# eBox_ACdetect.net
KiCad netlist of a schematic drawn in Altium Designer
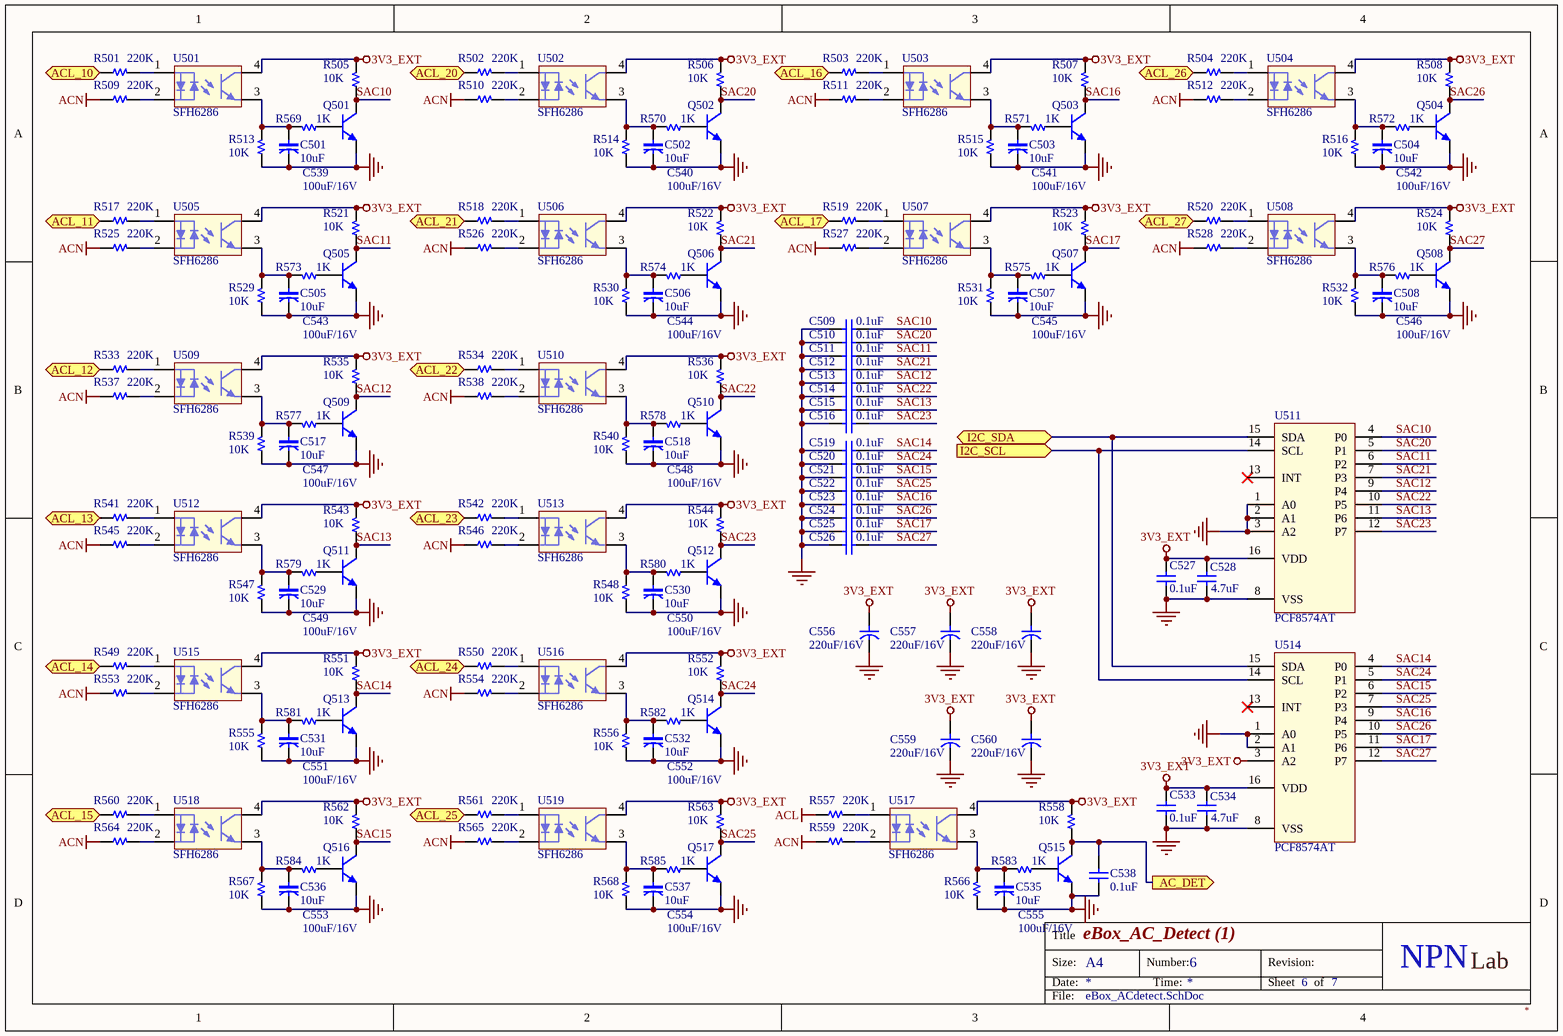
[diagram p0: eBox_ACdetect.SchDoc]

(export (version "E")
  (design (tool "Eeschema 10.0.6"))
  (components
    (comp (ref "C501")
      (value "10uF")
      (footprint "C 0805")
      (description "CAP CER 0.1UF 50V X7R 0805")
      (libsource (lib "chipfc_altium_libs") (part "Capacitor NP"))
    )
    (comp (ref "C502")
      (value "10uF")
      (footprint "C 0805")
      (description "CAP CER 0.1UF 50V X7R 0805")
      (libsource (lib "chipfc_altium_libs") (part "Capacitor NP"))
    )
    (comp (ref "C503")
      (value "10uF")
      (footprint "C 0805")
      (description "CAP CER 0.1UF 50V X7R 0805")
      (libsource (lib "chipfc_altium_libs") (part "Capacitor NP"))
    )
    (comp (ref "C504")
      (value "10uF")
      (footprint "C 0805")
      (description "CAP CER 0.1UF 50V X7R 0805")
      (libsource (lib "chipfc_altium_libs") (part "Capacitor NP"))
    )
    (comp (ref "C505")
      (value "10uF")
      (footprint "C 0805")
      (description "CAP CER 0.1UF 50V X7R 0805")
      (libsource (lib "chipfc_altium_libs") (part "Capacitor NP"))
    )
    (comp (ref "C506")
      (value "10uF")
      (footprint "C 0805")
      (description "CAP CER 0.1UF 50V X7R 0805")
      (libsource (lib "chipfc_altium_libs") (part "Capacitor NP"))
    )
    (comp (ref "C507")
      (value "10uF")
      (footprint "C 0805")
      (description "CAP CER 0.1UF 50V X7R 0805")
      (libsource (lib "chipfc_altium_libs") (part "Capacitor NP"))
    )
    (comp (ref "C508")
      (value "10uF")
      (footprint "C 0805")
      (description "CAP CER 0.1UF 50V X7R 0805")
      (libsource (lib "chipfc_altium_libs") (part "Capacitor NP"))
    )
    (comp (ref "C509")
      (value "0.1uF")
      (footprint "C 0805")
      (description "CAP CER 0.1UF 50V X7R 0805")
      (libsource (lib "chipfc_altium_libs") (part "Capacitor NP"))
    )
    (comp (ref "C510")
      (value "0.1uF")
      (footprint "C 0805")
      (description "CAP CER 0.1UF 50V X7R 0805")
      (libsource (lib "chipfc_altium_libs") (part "Capacitor NP"))
    )
    (comp (ref "C511")
      (value "0.1uF")
      (footprint "C 0805")
      (description "CAP CER 0.1UF 50V X7R 0805")
      (libsource (lib "chipfc_altium_libs") (part "Capacitor NP"))
    )
    (comp (ref "C512")
      (value "0.1uF")
      (footprint "C 0805")
      (description "CAP CER 0.1UF 50V X7R 0805")
      (libsource (lib "chipfc_altium_libs") (part "Capacitor NP"))
    )
    (comp (ref "C513")
      (value "0.1uF")
      (footprint "C 0805")
      (description "CAP CER 0.1UF 50V X7R 0805")
      (libsource (lib "chipfc_altium_libs") (part "Capacitor NP"))
    )
    (comp (ref "C514")
      (value "0.1uF")
      (footprint "C 0805")
      (description "CAP CER 0.1UF 50V X7R 0805")
      (libsource (lib "chipfc_altium_libs") (part "Capacitor NP"))
    )
    (comp (ref "C515")
      (value "0.1uF")
      (footprint "C 0805")
      (description "CAP CER 0.1UF 50V X7R 0805")
      (libsource (lib "chipfc_altium_libs") (part "Capacitor NP"))
    )
    (comp (ref "C516")
      (value "0.1uF")
      (footprint "C 0805")
      (description "CAP CER 0.1UF 50V X7R 0805")
      (libsource (lib "chipfc_altium_libs") (part "Capacitor NP"))
    )
    (comp (ref "C517")
      (value "10uF")
      (footprint "C 0805")
      (description "CAP CER 0.1UF 50V X7R 0805")
      (libsource (lib "chipfc_altium_libs") (part "Capacitor NP"))
    )
    (comp (ref "C518")
      (value "10uF")
      (footprint "C 0805")
      (description "CAP CER 0.1UF 50V X7R 0805")
      (libsource (lib "chipfc_altium_libs") (part "Capacitor NP"))
    )
    (comp (ref "C519")
      (value "0.1uF")
      (footprint "C 0805")
      (description "CAP CER 0.1UF 50V X7R 0805")
      (libsource (lib "chipfc_altium_libs") (part "Capacitor NP"))
    )
    (comp (ref "C520")
      (value "0.1uF")
      (footprint "C 0805")
      (description "CAP CER 0.1UF 50V X7R 0805")
      (libsource (lib "chipfc_altium_libs") (part "Capacitor NP"))
    )
    (comp (ref "C521")
      (value "0.1uF")
      (footprint "C 0805")
      (description "CAP CER 0.1UF 50V X7R 0805")
      (libsource (lib "chipfc_altium_libs") (part "Capacitor NP"))
    )
    (comp (ref "C522")
      (value "0.1uF")
      (footprint "C 0805")
      (description "CAP CER 0.1UF 50V X7R 0805")
      (libsource (lib "chipfc_altium_libs") (part "Capacitor NP"))
    )
    (comp (ref "C523")
      (value "0.1uF")
      (footprint "C 0805")
      (description "CAP CER 0.1UF 50V X7R 0805")
      (libsource (lib "chipfc_altium_libs") (part "Capacitor NP"))
    )
    (comp (ref "C524")
      (value "0.1uF")
      (footprint "C 0805")
      (description "CAP CER 0.1UF 50V X7R 0805")
      (libsource (lib "chipfc_altium_libs") (part "Capacitor NP"))
    )
    (comp (ref "C525")
      (value "0.1uF")
      (footprint "C 0805")
      (description "CAP CER 0.1UF 50V X7R 0805")
      (libsource (lib "chipfc_altium_libs") (part "Capacitor NP"))
    )
    (comp (ref "C526")
      (value "0.1uF")
      (footprint "C 0805")
      (description "CAP CER 0.1UF 50V X7R 0805")
      (libsource (lib "chipfc_altium_libs") (part "Capacitor NP"))
    )
    (comp (ref "C527")
      (value "0.1uF")
      (footprint "C 0603")
      (description "CAP CER 0.1UF 50V X7R 0603")
      (libsource (lib "chipfc_altium_libs") (part "Capacitor NP"))
    )
    (comp (ref "C528")
      (value "4.7uF")
      (footprint "C 0603")
      (description "CAP CER 4.7UF 50V X7R 0603")
      (libsource (lib "chipfc_altium_libs") (part "Capacitor NP"))
    )
    (comp (ref "C529")
      (value "10uF")
      (footprint "C 0805")
      (description "CAP CER 0.1UF 50V X7R 0805")
      (libsource (lib "chipfc_altium_libs") (part "Capacitor NP"))
    )
    (comp (ref "C530")
      (value "10uF")
      (footprint "C 0805")
      (description "CAP CER 0.1UF 50V X7R 0805")
      (libsource (lib "chipfc_altium_libs") (part "Capacitor NP"))
    )
    (comp (ref "C531")
      (value "10uF")
      (footprint "C 0805")
      (description "CAP CER 0.1UF 50V X7R 0805")
      (libsource (lib "chipfc_altium_libs") (part "Capacitor NP"))
    )
    (comp (ref "C532")
      (value "10uF")
      (footprint "C 0805")
      (description "CAP CER 0.1UF 50V X7R 0805")
      (libsource (lib "chipfc_altium_libs") (part "Capacitor NP"))
    )
    (comp (ref "C533")
      (value "0.1uF")
      (footprint "C 0603")
      (description "CAP CER 0.1UF 50V X7R 0603")
      (libsource (lib "chipfc_altium_libs") (part "Capacitor NP"))
    )
    (comp (ref "C534")
      (value "4.7uF")
      (footprint "C 0603")
      (description "CAP CER 4.7UF 50V X7R 0603")
      (libsource (lib "chipfc_altium_libs") (part "Capacitor NP"))
    )
    (comp (ref "C535")
      (value "10uF")
      (footprint "C 0805")
      (description "CAP CER 0.1UF 50V X7R 0805")
      (libsource (lib "chipfc_altium_libs") (part "Capacitor NP"))
    )
    (comp (ref "C536")
      (value "10uF")
      (footprint "C 0805")
      (description "CAP CER 0.1UF 50V X7R 0805")
      (libsource (lib "chipfc_altium_libs") (part "Capacitor NP"))
    )
    (comp (ref "C537")
      (value "10uF")
      (footprint "C 0805")
      (description "CAP CER 0.1UF 50V X7R 0805")
      (libsource (lib "chipfc_altium_libs") (part "Capacitor NP"))
    )
    (comp (ref "C538")
      (value "0.1uF")
      (footprint "C 0805")
      (description "CAP CER 0.1UF 50V X7R 0805")
      (libsource (lib "chipfc_altium_libs") (part "Capacitor NP"))
    )
    (comp (ref "C539")
      (value "100uF/16V")
      (footprint "CYL/D.200/LS.75")
      (description "Capacitor pol")
      (libsource (lib "chipfc_altium_libs") (part "Capacitor"))
    )
    (comp (ref "C540")
      (value "100uF/16V")
      (footprint "CYL/D.200/LS.75")
      (description "Capacitor pol")
      (libsource (lib "chipfc_altium_libs") (part "Capacitor"))
    )
    (comp (ref "C541")
      (value "100uF/16V")
      (footprint "CYL/D.200/LS.75")
      (description "Capacitor pol")
      (libsource (lib "chipfc_altium_libs") (part "Capacitor"))
    )
    (comp (ref "C542")
      (value "100uF/16V")
      (footprint "CYL/D.200/LS.75")
      (description "Capacitor pol")
      (libsource (lib "chipfc_altium_libs") (part "Capacitor"))
    )
    (comp (ref "C543")
      (value "100uF/16V")
      (footprint "CYL/D.200/LS.75")
      (description "Capacitor pol")
      (libsource (lib "chipfc_altium_libs") (part "Capacitor"))
    )
    (comp (ref "C544")
      (value "100uF/16V")
      (footprint "CYL/D.200/LS.75")
      (description "Capacitor pol")
      (libsource (lib "chipfc_altium_libs") (part "Capacitor"))
    )
    (comp (ref "C545")
      (value "100uF/16V")
      (footprint "CYL/D.200/LS.75")
      (description "Capacitor pol")
      (libsource (lib "chipfc_altium_libs") (part "Capacitor"))
    )
    (comp (ref "C546")
      (value "100uF/16V")
      (footprint "CYL/D.200/LS.75")
      (description "Capacitor pol")
      (libsource (lib "chipfc_altium_libs") (part "Capacitor"))
    )
    (comp (ref "C547")
      (value "100uF/16V")
      (footprint "CYL/D.200/LS.75")
      (description "Capacitor pol")
      (libsource (lib "chipfc_altium_libs") (part "Capacitor"))
    )
    (comp (ref "C548")
      (value "100uF/16V")
      (footprint "CYL/D.200/LS.75")
      (description "Capacitor pol")
      (libsource (lib "chipfc_altium_libs") (part "Capacitor"))
    )
    (comp (ref "C549")
      (value "100uF/16V")
      (footprint "CYL/D.200/LS.75")
      (description "Capacitor pol")
      (libsource (lib "chipfc_altium_libs") (part "Capacitor"))
    )
    (comp (ref "C550")
      (value "100uF/16V")
      (footprint "CYL/D.200/LS.75")
      (description "Capacitor pol")
      (libsource (lib "chipfc_altium_libs") (part "Capacitor"))
    )
    (comp (ref "C551")
      (value "100uF/16V")
      (footprint "CYL/D.200/LS.75")
      (description "Capacitor pol")
      (libsource (lib "chipfc_altium_libs") (part "Capacitor"))
    )
    (comp (ref "C552")
      (value "100uF/16V")
      (footprint "CYL/D.200/LS.75")
      (description "Capacitor pol")
      (libsource (lib "chipfc_altium_libs") (part "Capacitor"))
    )
    (comp (ref "C553")
      (value "100uF/16V")
      (footprint "CYL/D.200/LS.75")
      (description "Capacitor pol")
      (libsource (lib "chipfc_altium_libs") (part "Capacitor"))
    )
    (comp (ref "C554")
      (value "100uF/16V")
      (footprint "CYL/D.200/LS.75")
      (description "Capacitor pol")
      (libsource (lib "chipfc_altium_libs") (part "Capacitor"))
    )
    (comp (ref "C555")
      (value "100uF/16V")
      (footprint "CYL/D.200/LS.75")
      (description "Capacitor pol")
      (libsource (lib "chipfc_altium_libs") (part "Capacitor"))
    )
    (comp (ref "C556")
      (value "220uF/16V")
      (footprint "CYL/D.250/LS.100")
      (description "CAP TANT 100UF 20% 16V 2917")
      (libsource (lib "") (part "Capacitor_1"))
    )
    (comp (ref "C557")
      (value "220uF/16V")
      (footprint "CYL/D.250/LS.100")
      (description "CAP TANT 100UF 20% 16V 2917")
      (libsource (lib "") (part "Capacitor_1"))
    )
    (comp (ref "C558")
      (value "220uF/16V")
      (footprint "CYL/D.250/LS.100")
      (description "CAP TANT 100UF 20% 16V 2917")
      (libsource (lib "") (part "Capacitor_1"))
    )
    (comp (ref "C559")
      (value "220uF/16V")
      (footprint "CYL/D.250/LS.100")
      (description "CAP TANT 100UF 20% 16V 2917")
      (libsource (lib "") (part "Capacitor_1"))
    )
    (comp (ref "C560")
      (value "220uF/16V")
      (footprint "CYL/D.250/LS.100")
      (description "CAP TANT 100UF 20% 16V 2917")
      (libsource (lib "") (part "Capacitor_1"))
    )
    (comp (ref "Q501")
      (value "MMBT3904LT1G")
      (footprint "SOT-23")
      (description "TRANS NPN 40V 0.2A SOT23")
      (libsource (lib "chipfc_altium_libs") (part "Transistor NPN"))
    )
    (comp (ref "Q502")
      (value "MMBT3904LT1G")
      (footprint "SOT-23")
      (description "TRANS NPN 40V 0.2A SOT23")
      (libsource (lib "chipfc_altium_libs") (part "Transistor NPN"))
    )
    (comp (ref "Q503")
      (value "MMBT3904LT1G")
      (footprint "SOT-23")
      (description "TRANS NPN 40V 0.2A SOT23")
      (libsource (lib "chipfc_altium_libs") (part "Transistor NPN"))
    )
    (comp (ref "Q504")
      (value "MMBT3904LT1G")
      (footprint "SOT-23")
      (description "TRANS NPN 40V 0.2A SOT23")
      (libsource (lib "chipfc_altium_libs") (part "Transistor NPN"))
    )
    (comp (ref "Q505")
      (value "MMBT3904LT1G")
      (footprint "SOT-23")
      (description "TRANS NPN 40V 0.2A SOT23")
      (libsource (lib "chipfc_altium_libs") (part "Transistor NPN"))
    )
    (comp (ref "Q506")
      (value "MMBT3904LT1G")
      (footprint "SOT-23")
      (description "TRANS NPN 40V 0.2A SOT23")
      (libsource (lib "chipfc_altium_libs") (part "Transistor NPN"))
    )
    (comp (ref "Q507")
      (value "MMBT3904LT1G")
      (footprint "SOT-23")
      (description "TRANS NPN 40V 0.2A SOT23")
      (libsource (lib "chipfc_altium_libs") (part "Transistor NPN"))
    )
    (comp (ref "Q508")
      (value "MMBT3904LT1G")
      (footprint "SOT-23")
      (description "TRANS NPN 40V 0.2A SOT23")
      (libsource (lib "chipfc_altium_libs") (part "Transistor NPN"))
    )
    (comp (ref "Q509")
      (value "MMBT3904LT1G")
      (footprint "SOT-23")
      (description "TRANS NPN 40V 0.2A SOT23")
      (libsource (lib "chipfc_altium_libs") (part "Transistor NPN"))
    )
    (comp (ref "Q510")
      (value "MMBT3904LT1G")
      (footprint "SOT-23")
      (description "TRANS NPN 40V 0.2A SOT23")
      (libsource (lib "chipfc_altium_libs") (part "Transistor NPN"))
    )
    (comp (ref "Q511")
      (value "MMBT3904LT1G")
      (footprint "SOT-23")
      (description "TRANS NPN 40V 0.2A SOT23")
      (libsource (lib "chipfc_altium_libs") (part "Transistor NPN"))
    )
    (comp (ref "Q512")
      (value "MMBT3904LT1G")
      (footprint "SOT-23")
      (description "TRANS NPN 40V 0.2A SOT23")
      (libsource (lib "chipfc_altium_libs") (part "Transistor NPN"))
    )
    (comp (ref "Q513")
      (value "MMBT3904LT1G")
      (footprint "SOT-23")
      (description "TRANS NPN 40V 0.2A SOT23")
      (libsource (lib "chipfc_altium_libs") (part "Transistor NPN"))
    )
    (comp (ref "Q514")
      (value "MMBT3904LT1G")
      (footprint "SOT-23")
      (description "TRANS NPN 40V 0.2A SOT23")
      (libsource (lib "chipfc_altium_libs") (part "Transistor NPN"))
    )
    (comp (ref "Q515")
      (value "MMBT3904LT1G")
      (footprint "SOT-23")
      (description "TRANS NPN 40V 0.2A SOT23")
      (libsource (lib "chipfc_altium_libs") (part "Transistor NPN"))
    )
    (comp (ref "Q516")
      (value "MMBT3904LT1G")
      (footprint "SOT-23")
      (description "TRANS NPN 40V 0.2A SOT23")
      (libsource (lib "chipfc_altium_libs") (part "Transistor NPN"))
    )
    (comp (ref "Q517")
      (value "MMBT3904LT1G")
      (footprint "SOT-23")
      (description "TRANS NPN 40V 0.2A SOT23")
      (libsource (lib "chipfc_altium_libs") (part "Transistor NPN"))
    )
    (comp (ref "R501")
      (value "220K")
      (footprint "R 0805")
      (description "RES SMD 220K OHM 1% 1/8W 0805")
      (libsource (lib "chipfc_altium_libs") (part "Resistor"))
    )
    (comp (ref "R502")
      (value "220K")
      (footprint "R 0805")
      (description "RES SMD 220K OHM 1% 1/8W 0805")
      (libsource (lib "chipfc_altium_libs") (part "Resistor"))
    )
    (comp (ref "R503")
      (value "220K")
      (footprint "R 0805")
      (description "RES SMD 220K OHM 1% 1/8W 0805")
      (libsource (lib "chipfc_altium_libs") (part "Resistor"))
    )
    (comp (ref "R504")
      (value "220K")
      (footprint "R 0805")
      (description "RES SMD 220K OHM 1% 1/8W 0805")
      (libsource (lib "chipfc_altium_libs") (part "Resistor"))
    )
    (comp (ref "R505")
      (value "10K")
      (footprint "R 0805")
      (description "RES SMD 10K OHM 1% 1/8W 0805")
      (libsource (lib "chipfc_altium_libs") (part "Resistor"))
    )
    (comp (ref "R506")
      (value "10K")
      (footprint "R 0805")
      (description "RES SMD 10K OHM 1% 1/8W 0805")
      (libsource (lib "chipfc_altium_libs") (part "Resistor"))
    )
    (comp (ref "R507")
      (value "10K")
      (footprint "R 0805")
      (description "RES SMD 10K OHM 1% 1/8W 0805")
      (libsource (lib "chipfc_altium_libs") (part "Resistor"))
    )
    (comp (ref "R508")
      (value "10K")
      (footprint "R 0805")
      (description "RES SMD 10K OHM 1% 1/8W 0805")
      (libsource (lib "chipfc_altium_libs") (part "Resistor"))
    )
    (comp (ref "R509")
      (value "220K")
      (footprint "R 0805")
      (description "RES SMD 220K OHM 1% 1/8W 0805")
      (libsource (lib "chipfc_altium_libs") (part "Resistor"))
    )
    (comp (ref "R510")
      (value "220K")
      (footprint "R 0805")
      (description "RES SMD 220K OHM 1% 1/8W 0805")
      (libsource (lib "chipfc_altium_libs") (part "Resistor"))
    )
    (comp (ref "R511")
      (value "220K")
      (footprint "R 0805")
      (description "RES SMD 220K OHM 1% 1/8W 0805")
      (libsource (lib "chipfc_altium_libs") (part "Resistor"))
    )
    (comp (ref "R512")
      (value "220K")
      (footprint "R 0805")
      (description "RES SMD 220K OHM 1% 1/8W 0805")
      (libsource (lib "chipfc_altium_libs") (part "Resistor"))
    )
    (comp (ref "R513")
      (value "10K")
      (footprint "R 0805")
      (description "RES SMD 10K OHM 1% 1/8W 0805")
      (libsource (lib "chipfc_altium_libs") (part "Resistor"))
    )
    (comp (ref "R514")
      (value "10K")
      (footprint "R 0805")
      (description "RES SMD 10K OHM 1% 1/8W 0805")
      (libsource (lib "chipfc_altium_libs") (part "Resistor"))
    )
    (comp (ref "R515")
      (value "10K")
      (footprint "R 0805")
      (description "RES SMD 10K OHM 1% 1/8W 0805")
      (libsource (lib "chipfc_altium_libs") (part "Resistor"))
    )
    (comp (ref "R516")
      (value "10K")
      (footprint "R 0805")
      (description "RES SMD 10K OHM 1% 1/8W 0805")
      (libsource (lib "chipfc_altium_libs") (part "Resistor"))
    )
    (comp (ref "R517")
      (value "220K")
      (footprint "R 0805")
      (description "RES SMD 220K OHM 1% 1/8W 0805")
      (libsource (lib "chipfc_altium_libs") (part "Resistor"))
    )
    (comp (ref "R518")
      (value "220K")
      (footprint "R 0805")
      (description "RES SMD 220K OHM 1% 1/8W 0805")
      (libsource (lib "chipfc_altium_libs") (part "Resistor"))
    )
    (comp (ref "R519")
      (value "220K")
      (footprint "R 0805")
      (description "RES SMD 220K OHM 1% 1/8W 0805")
      (libsource (lib "chipfc_altium_libs") (part "Resistor"))
    )
    (comp (ref "R520")
      (value "220K")
      (footprint "R 0805")
      (description "RES SMD 220K OHM 1% 1/8W 0805")
      (libsource (lib "chipfc_altium_libs") (part "Resistor"))
    )
    (comp (ref "R521")
      (value "10K")
      (footprint "R 0805")
      (description "RES SMD 10K OHM 1% 1/8W 0805")
      (libsource (lib "chipfc_altium_libs") (part "Resistor"))
    )
    (comp (ref "R522")
      (value "10K")
      (footprint "R 0805")
      (description "RES SMD 10K OHM 1% 1/8W 0805")
      (libsource (lib "chipfc_altium_libs") (part "Resistor"))
    )
    (comp (ref "R523")
      (value "10K")
      (footprint "R 0805")
      (description "RES SMD 10K OHM 1% 1/8W 0805")
      (libsource (lib "chipfc_altium_libs") (part "Resistor"))
    )
    (comp (ref "R524")
      (value "10K")
      (footprint "R 0805")
      (description "RES SMD 10K OHM 1% 1/8W 0805")
      (libsource (lib "chipfc_altium_libs") (part "Resistor"))
    )
    (comp (ref "R525")
      (value "220K")
      (footprint "R 0805")
      (description "RES SMD 220K OHM 1% 1/8W 0805")
      (libsource (lib "chipfc_altium_libs") (part "Resistor"))
    )
    (comp (ref "R526")
      (value "220K")
      (footprint "R 0805")
      (description "RES SMD 220K OHM 1% 1/8W 0805")
      (libsource (lib "chipfc_altium_libs") (part "Resistor"))
    )
    (comp (ref "R527")
      (value "220K")
      (footprint "R 0805")
      (description "RES SMD 220K OHM 1% 1/8W 0805")
      (libsource (lib "chipfc_altium_libs") (part "Resistor"))
    )
    (comp (ref "R528")
      (value "220K")
      (footprint "R 0805")
      (description "RES SMD 220K OHM 1% 1/8W 0805")
      (libsource (lib "chipfc_altium_libs") (part "Resistor"))
    )
    (comp (ref "R529")
      (value "10K")
      (footprint "R 0805")
      (description "RES SMD 10K OHM 1% 1/8W 0805")
      (libsource (lib "chipfc_altium_libs") (part "Resistor"))
    )
    (comp (ref "R530")
      (value "10K")
      (footprint "R 0805")
      (description "RES SMD 10K OHM 1% 1/8W 0805")
      (libsource (lib "chipfc_altium_libs") (part "Resistor"))
    )
    (comp (ref "R531")
      (value "10K")
      (footprint "R 0805")
      (description "RES SMD 10K OHM 1% 1/8W 0805")
      (libsource (lib "chipfc_altium_libs") (part "Resistor"))
    )
    (comp (ref "R532")
      (value "10K")
      (footprint "R 0805")
      (description "RES SMD 10K OHM 1% 1/8W 0805")
      (libsource (lib "chipfc_altium_libs") (part "Resistor"))
    )
    (comp (ref "R533")
      (value "220K")
      (footprint "R 0805")
      (description "RES SMD 220K OHM 1% 1/8W 0805")
      (libsource (lib "chipfc_altium_libs") (part "Resistor"))
    )
    (comp (ref "R534")
      (value "220K")
      (footprint "R 0805")
      (description "RES SMD 220K OHM 1% 1/8W 0805")
      (libsource (lib "chipfc_altium_libs") (part "Resistor"))
    )
    (comp (ref "R535")
      (value "10K")
      (footprint "R 0805")
      (description "RES SMD 10K OHM 1% 1/8W 0805")
      (libsource (lib "chipfc_altium_libs") (part "Resistor"))
    )
    (comp (ref "R536")
      (value "10K")
      (footprint "R 0805")
      (description "RES SMD 10K OHM 1% 1/8W 0805")
      (libsource (lib "chipfc_altium_libs") (part "Resistor"))
    )
    (comp (ref "R537")
      (value "220K")
      (footprint "R 0805")
      (description "RES SMD 220K OHM 1% 1/8W 0805")
      (libsource (lib "chipfc_altium_libs") (part "Resistor"))
    )
    (comp (ref "R538")
      (value "220K")
      (footprint "R 0805")
      (description "RES SMD 220K OHM 1% 1/8W 0805")
      (libsource (lib "chipfc_altium_libs") (part "Resistor"))
    )
    (comp (ref "R539")
      (value "10K")
      (footprint "R 0805")
      (description "RES SMD 10K OHM 1% 1/8W 0805")
      (libsource (lib "chipfc_altium_libs") (part "Resistor"))
    )
    (comp (ref "R540")
      (value "10K")
      (footprint "R 0805")
      (description "RES SMD 10K OHM 1% 1/8W 0805")
      (libsource (lib "chipfc_altium_libs") (part "Resistor"))
    )
    (comp (ref "R541")
      (value "220K")
      (footprint "R 0805")
      (description "RES SMD 220K OHM 1% 1/8W 0805")
      (libsource (lib "chipfc_altium_libs") (part "Resistor"))
    )
    (comp (ref "R542")
      (value "220K")
      (footprint "R 0805")
      (description "RES SMD 220K OHM 1% 1/8W 0805")
      (libsource (lib "chipfc_altium_libs") (part "Resistor"))
    )
    (comp (ref "R543")
      (value "10K")
      (footprint "R 0805")
      (description "RES SMD 10K OHM 1% 1/8W 0805")
      (libsource (lib "chipfc_altium_libs") (part "Resistor"))
    )
    (comp (ref "R544")
      (value "10K")
      (footprint "R 0805")
      (description "RES SMD 10K OHM 1% 1/8W 0805")
      (libsource (lib "chipfc_altium_libs") (part "Resistor"))
    )
    (comp (ref "R545")
      (value "220K")
      (footprint "R 0805")
      (description "RES SMD 220K OHM 1% 1/8W 0805")
      (libsource (lib "chipfc_altium_libs") (part "Resistor"))
    )
    (comp (ref "R546")
      (value "220K")
      (footprint "R 0805")
      (description "RES SMD 220K OHM 1% 1/8W 0805")
      (libsource (lib "chipfc_altium_libs") (part "Resistor"))
    )
    (comp (ref "R547")
      (value "10K")
      (footprint "R 0805")
      (description "RES SMD 10K OHM 1% 1/8W 0805")
      (libsource (lib "chipfc_altium_libs") (part "Resistor"))
    )
    (comp (ref "R548")
      (value "10K")
      (footprint "R 0805")
      (description "RES SMD 10K OHM 1% 1/8W 0805")
      (libsource (lib "chipfc_altium_libs") (part "Resistor"))
    )
    (comp (ref "R549")
      (value "220K")
      (footprint "R 0805")
      (description "RES SMD 220K OHM 1% 1/8W 0805")
      (libsource (lib "chipfc_altium_libs") (part "Resistor"))
    )
    (comp (ref "R550")
      (value "220K")
      (footprint "R 0805")
      (description "RES SMD 220K OHM 1% 1/8W 0805")
      (libsource (lib "chipfc_altium_libs") (part "Resistor"))
    )
    (comp (ref "R551")
      (value "10K")
      (footprint "R 0805")
      (description "RES SMD 10K OHM 1% 1/8W 0805")
      (libsource (lib "chipfc_altium_libs") (part "Resistor"))
    )
    (comp (ref "R552")
      (value "10K")
      (footprint "R 0805")
      (description "RES SMD 10K OHM 1% 1/8W 0805")
      (libsource (lib "chipfc_altium_libs") (part "Resistor"))
    )
    (comp (ref "R553")
      (value "220K")
      (footprint "R 0805")
      (description "RES SMD 220K OHM 1% 1/8W 0805")
      (libsource (lib "chipfc_altium_libs") (part "Resistor"))
    )
    (comp (ref "R554")
      (value "220K")
      (footprint "R 0805")
      (description "RES SMD 220K OHM 1% 1/8W 0805")
      (libsource (lib "chipfc_altium_libs") (part "Resistor"))
    )
    (comp (ref "R555")
      (value "10K")
      (footprint "R 0805")
      (description "RES SMD 10K OHM 1% 1/8W 0805")
      (libsource (lib "chipfc_altium_libs") (part "Resistor"))
    )
    (comp (ref "R556")
      (value "10K")
      (footprint "R 0805")
      (description "RES SMD 10K OHM 1% 1/8W 0805")
      (libsource (lib "chipfc_altium_libs") (part "Resistor"))
    )
    (comp (ref "R557")
      (value "220K")
      (footprint "R 0805")
      (description "RES SMD 220K OHM 1% 1/8W 0805")
      (libsource (lib "chipfc_altium_libs") (part "Resistor"))
    )
    (comp (ref "R558")
      (value "10K")
      (footprint "R 0805")
      (description "RES SMD 10K OHM 1% 1/8W 0805")
      (libsource (lib "chipfc_altium_libs") (part "Resistor"))
    )
    (comp (ref "R559")
      (value "220K")
      (footprint "R 0805")
      (description "RES SMD 220K OHM 1% 1/8W 0805")
      (libsource (lib "chipfc_altium_libs") (part "Resistor"))
    )
    (comp (ref "R560")
      (value "220K")
      (footprint "R 0805")
      (description "RES SMD 220K OHM 1% 1/8W 0805")
      (libsource (lib "chipfc_altium_libs") (part "Resistor"))
    )
    (comp (ref "R561")
      (value "220K")
      (footprint "R 0805")
      (description "RES SMD 220K OHM 1% 1/8W 0805")
      (libsource (lib "chipfc_altium_libs") (part "Resistor"))
    )
    (comp (ref "R562")
      (value "10K")
      (footprint "R 0805")
      (description "RES SMD 10K OHM 1% 1/8W 0805")
      (libsource (lib "chipfc_altium_libs") (part "Resistor"))
    )
    (comp (ref "R563")
      (value "10K")
      (footprint "R 0805")
      (description "RES SMD 10K OHM 1% 1/8W 0805")
      (libsource (lib "chipfc_altium_libs") (part "Resistor"))
    )
    (comp (ref "R564")
      (value "220K")
      (footprint "R 0805")
      (description "RES SMD 220K OHM 1% 1/8W 0805")
      (libsource (lib "chipfc_altium_libs") (part "Resistor"))
    )
    (comp (ref "R565")
      (value "220K")
      (footprint "R 0805")
      (description "RES SMD 220K OHM 1% 1/8W 0805")
      (libsource (lib "chipfc_altium_libs") (part "Resistor"))
    )
    (comp (ref "R566")
      (value "10K")
      (footprint "R 0805")
      (description "RES SMD 10K OHM 1% 1/8W 0805")
      (libsource (lib "chipfc_altium_libs") (part "Resistor"))
    )
    (comp (ref "R567")
      (value "10K")
      (footprint "R 0805")
      (description "RES SMD 10K OHM 1% 1/8W 0805")
      (libsource (lib "chipfc_altium_libs") (part "Resistor"))
    )
    (comp (ref "R568")
      (value "10K")
      (footprint "R 0805")
      (description "RES SMD 10K OHM 1% 1/8W 0805")
      (libsource (lib "chipfc_altium_libs") (part "Resistor"))
    )
    (comp (ref "R569")
      (value "1K")
      (footprint "R 0805")
      (description "RES SMD 10K OHM 1% 1/8W 0805")
      (libsource (lib "chipfc_altium_libs") (part "Resistor"))
    )
    (comp (ref "R570")
      (value "1K")
      (footprint "R 0805")
      (description "RES SMD 10K OHM 1% 1/8W 0805")
      (libsource (lib "chipfc_altium_libs") (part "Resistor"))
    )
    (comp (ref "R571")
      (value "1K")
      (footprint "R 0805")
      (description "RES SMD 10K OHM 1% 1/8W 0805")
      (libsource (lib "chipfc_altium_libs") (part "Resistor"))
    )
    (comp (ref "R572")
      (value "1K")
      (footprint "R 0805")
      (description "RES SMD 10K OHM 1% 1/8W 0805")
      (libsource (lib "chipfc_altium_libs") (part "Resistor"))
    )
    (comp (ref "R573")
      (value "1K")
      (footprint "R 0805")
      (description "RES SMD 10K OHM 1% 1/8W 0805")
      (libsource (lib "chipfc_altium_libs") (part "Resistor"))
    )
    (comp (ref "R574")
      (value "1K")
      (footprint "R 0805")
      (description "RES SMD 10K OHM 1% 1/8W 0805")
      (libsource (lib "chipfc_altium_libs") (part "Resistor"))
    )
    (comp (ref "R575")
      (value "1K")
      (footprint "R 0805")
      (description "RES SMD 10K OHM 1% 1/8W 0805")
      (libsource (lib "chipfc_altium_libs") (part "Resistor"))
    )
    (comp (ref "R576")
      (value "1K")
      (footprint "R 0805")
      (description "RES SMD 10K OHM 1% 1/8W 0805")
      (libsource (lib "chipfc_altium_libs") (part "Resistor"))
    )
    (comp (ref "R577")
      (value "1K")
      (footprint "R 0805")
      (description "RES SMD 10K OHM 1% 1/8W 0805")
      (libsource (lib "chipfc_altium_libs") (part "Resistor"))
    )
    (comp (ref "R578")
      (value "1K")
      (footprint "R 0805")
      (description "RES SMD 10K OHM 1% 1/8W 0805")
      (libsource (lib "chipfc_altium_libs") (part "Resistor"))
    )
    (comp (ref "R579")
      (value "1K")
      (footprint "R 0805")
      (description "RES SMD 10K OHM 1% 1/8W 0805")
      (libsource (lib "chipfc_altium_libs") (part "Resistor"))
    )
    (comp (ref "R580")
      (value "1K")
      (footprint "R 0805")
      (description "RES SMD 10K OHM 1% 1/8W 0805")
      (libsource (lib "chipfc_altium_libs") (part "Resistor"))
    )
    (comp (ref "R581")
      (value "1K")
      (footprint "R 0805")
      (description "RES SMD 10K OHM 1% 1/8W 0805")
      (libsource (lib "chipfc_altium_libs") (part "Resistor"))
    )
    (comp (ref "R582")
      (value "1K")
      (footprint "R 0805")
      (description "RES SMD 10K OHM 1% 1/8W 0805")
      (libsource (lib "chipfc_altium_libs") (part "Resistor"))
    )
    (comp (ref "R583")
      (value "1K")
      (footprint "R 0805")
      (description "RES SMD 10K OHM 1% 1/8W 0805")
      (libsource (lib "chipfc_altium_libs") (part "Resistor"))
    )
    (comp (ref "R584")
      (value "1K")
      (footprint "R 0805")
      (description "RES SMD 10K OHM 1% 1/8W 0805")
      (libsource (lib "chipfc_altium_libs") (part "Resistor"))
    )
    (comp (ref "R585")
      (value "1K")
      (footprint "R 0805")
      (description "RES SMD 10K OHM 1% 1/8W 0805")
      (libsource (lib "chipfc_altium_libs") (part "Resistor"))
    )
    (comp (ref "U501")
      (value "SFH6286")
      (footprint "SOP4 - SFH6286")
      (libsource (lib "chipfc_altium_libs") (part "SFH6286"))
    )
    (comp (ref "U502")
      (value "SFH6286")
      (footprint "SOP4 - SFH6286")
      (libsource (lib "chipfc_altium_libs") (part "SFH6286"))
    )
    (comp (ref "U503")
      (value "SFH6286")
      (footprint "SOP4 - SFH6286")
      (libsource (lib "chipfc_altium_libs") (part "SFH6286"))
    )
    (comp (ref "U504")
      (value "SFH6286")
      (footprint "SOP4 - SFH6286")
      (libsource (lib "chipfc_altium_libs") (part "SFH6286"))
    )
    (comp (ref "U505")
      (value "SFH6286")
      (footprint "SOP4 - SFH6286")
      (libsource (lib "chipfc_altium_libs") (part "SFH6286"))
    )
    (comp (ref "U506")
      (value "SFH6286")
      (footprint "SOP4 - SFH6286")
      (libsource (lib "chipfc_altium_libs") (part "SFH6286"))
    )
    (comp (ref "U507")
      (value "SFH6286")
      (footprint "SOP4 - SFH6286")
      (libsource (lib "chipfc_altium_libs") (part "SFH6286"))
    )
    (comp (ref "U508")
      (value "SFH6286")
      (footprint "SOP4 - SFH6286")
      (libsource (lib "chipfc_altium_libs") (part "SFH6286"))
    )
    (comp (ref "U509")
      (value "SFH6286")
      (footprint "SOP4 - SFH6286")
      (libsource (lib "chipfc_altium_libs") (part "SFH6286"))
    )
    (comp (ref "U510")
      (value "SFH6286")
      (footprint "SOP4 - SFH6286")
      (libsource (lib "chipfc_altium_libs") (part "SFH6286"))
    )
    (comp (ref "U511")
      (value "PCF8574AT")
      (footprint "SO16/PCF8574AT")
      (description "Remote 8-bit I/O expander for I2C-bus with interrupt")
      (fields (field (name "PART NO") "PCF8574AT/3"))
      (libsource (lib "chipfc_altium_libs") (part "PCF8574AT"))
    )
    (comp (ref "U512")
      (value "SFH6286")
      (footprint "SOP4 - SFH6286")
      (libsource (lib "chipfc_altium_libs") (part "SFH6286"))
    )
    (comp (ref "U513")
      (value "SFH6286")
      (footprint "SOP4 - SFH6286")
      (libsource (lib "chipfc_altium_libs") (part "SFH6286"))
    )
    (comp (ref "U514")
      (value "PCF8574AT")
      (footprint "SO16/PCF8574AT")
      (description "Remote 8-bit I/O expander for I2C-bus with interrupt")
      (fields (field (name "PART NO") "PCF8574AT/3"))
      (libsource (lib "chipfc_altium_libs") (part "PCF8574AT"))
    )
    (comp (ref "U515")
      (value "SFH6286")
      (footprint "SOP4 - SFH6286")
      (libsource (lib "chipfc_altium_libs") (part "SFH6286"))
    )
    (comp (ref "U516")
      (value "SFH6286")
      (footprint "SOP4 - SFH6286")
      (libsource (lib "chipfc_altium_libs") (part "SFH6286"))
    )
    (comp (ref "U517")
      (value "SFH6286")
      (footprint "SOP4 - SFH6286")
      (libsource (lib "chipfc_altium_libs") (part "SFH6286"))
    )
    (comp (ref "U518")
      (value "SFH6286")
      (footprint "SOP4 - SFH6286")
      (libsource (lib "chipfc_altium_libs") (part "SFH6286"))
    )
    (comp (ref "U519")
      (value "SFH6286")
      (footprint "SOP4 - SFH6286")
      (libsource (lib "chipfc_altium_libs") (part "SFH6286"))
    )
  )
  (nets
    (net (code "1") (name "/ACL_10") (class "Default")
      (node (ref "R501") (pin "1") (pinfunction "1_1") (pintype "passive"))
    )
    (net (code "2") (name "/ACL_11") (class "Default")
      (node (ref "R517") (pin "1") (pinfunction "1_1") (pintype "passive"))
    )
    (net (code "3") (name "/ACL_12") (class "Default")
      (node (ref "R533") (pin "1") (pinfunction "1_1") (pintype "passive"))
    )
    (net (code "4") (name "/ACL_13") (class "Default")
      (node (ref "R541") (pin "1") (pinfunction "1_1") (pintype "passive"))
    )
    (net (code "5") (name "/ACL_14") (class "Default")
      (node (ref "R549") (pin "1") (pinfunction "1_1") (pintype "passive"))
    )
    (net (code "6") (name "/ACL_15") (class "Default")
      (node (ref "R560") (pin "1") (pinfunction "1_1") (pintype "passive"))
    )
    (net (code "7") (name "/ACL_16") (class "Default")
      (node (ref "R503") (pin "1") (pinfunction "1_1") (pintype "passive"))
    )
    (net (code "8") (name "/ACL_17") (class "Default")
      (node (ref "R519") (pin "1") (pinfunction "1_1") (pintype "passive"))
    )
    (net (code "9") (name "/ACL_20") (class "Default")
      (node (ref "R502") (pin "1") (pinfunction "1_1") (pintype "passive"))
    )
    (net (code "10") (name "/ACL_21") (class "Default")
      (node (ref "R518") (pin "1") (pinfunction "1_1") (pintype "passive"))
    )
    (net (code "11") (name "/ACL_22") (class "Default")
      (node (ref "R534") (pin "1") (pinfunction "1_1") (pintype "passive"))
    )
    (net (code "12") (name "/ACL_23") (class "Default")
      (node (ref "R542") (pin "1") (pinfunction "1_1") (pintype "passive"))
    )
    (net (code "13") (name "/ACL_24") (class "Default")
      (node (ref "R550") (pin "1") (pinfunction "1_1") (pintype "passive"))
    )
    (net (code "14") (name "/ACL_25") (class "Default")
      (node (ref "R561") (pin "1") (pinfunction "1_1") (pintype "passive"))
    )
    (net (code "15") (name "/ACL_26") (class "Default")
      (node (ref "R504") (pin "1") (pinfunction "1_1") (pintype "passive"))
    )
    (net (code "16") (name "/ACL_27") (class "Default")
      (node (ref "R520") (pin "1") (pinfunction "1_1") (pintype "passive"))
    )
    (net (code "17") (name "/AC_DET") (class "Default")
      (node (ref "C538") (pin "2") (pinfunction "2_2") (pintype "passive"))
      (node (ref "Q515") (pin "3") (pinfunction "C_3") (pintype "passive"))
      (node (ref "R558") (pin "1") (pinfunction "1_1") (pintype "passive"))
    )
    (net (code "18") (name "/I2C_SCL") (class "Default")
      (node (ref "U511") (pin "14") (pinfunction "SCL_14") (pintype "passive"))
      (node (ref "U514") (pin "14") (pinfunction "SCL_14") (pintype "passive"))
    )
    (net (code "19") (name "/I2C_SDA") (class "Default")
      (node (ref "U511") (pin "15") (pinfunction "SDA_15") (pintype "passive"))
      (node (ref "U514") (pin "15") (pinfunction "SDA_15") (pintype "passive"))
    )
    (net (code "20") (name "/SAC10") (class "Default")
      (node (ref "C509") (pin "2") (pinfunction "2_2") (pintype "passive"))
      (node (ref "Q501") (pin "3") (pinfunction "C_3") (pintype "passive"))
      (node (ref "R505") (pin "1") (pinfunction "1_1") (pintype "passive"))
      (node (ref "U511") (pin "4") (pinfunction "P0_4") (pintype "passive"))
    )
    (net (code "21") (name "/SAC11") (class "Default")
      (node (ref "C511") (pin "2") (pinfunction "2_2") (pintype "passive"))
      (node (ref "Q505") (pin "3") (pinfunction "C_3") (pintype "passive"))
      (node (ref "R521") (pin "1") (pinfunction "1_1") (pintype "passive"))
      (node (ref "U511") (pin "6") (pinfunction "P2_6") (pintype "passive"))
    )
    (net (code "22") (name "/SAC12") (class "Default")
      (node (ref "C513") (pin "2") (pinfunction "2_2") (pintype "passive"))
      (node (ref "Q509") (pin "3") (pinfunction "C_3") (pintype "passive"))
      (node (ref "R535") (pin "1") (pinfunction "1_1") (pintype "passive"))
      (node (ref "U511") (pin "9") (pinfunction "P4_9") (pintype "passive"))
    )
    (net (code "23") (name "/SAC13") (class "Default")
      (node (ref "C515") (pin "2") (pinfunction "2_2") (pintype "passive"))
      (node (ref "Q511") (pin "3") (pinfunction "C_3") (pintype "passive"))
      (node (ref "R543") (pin "1") (pinfunction "1_1") (pintype "passive"))
      (node (ref "U511") (pin "11") (pinfunction "P6_11") (pintype "passive"))
    )
    (net (code "24") (name "/SAC14") (class "Default")
      (node (ref "C519") (pin "2") (pinfunction "2_2") (pintype "passive"))
      (node (ref "Q513") (pin "3") (pinfunction "C_3") (pintype "passive"))
      (node (ref "R551") (pin "1") (pinfunction "1_1") (pintype "passive"))
      (node (ref "U514") (pin "4") (pinfunction "P0_4") (pintype "passive"))
    )
    (net (code "25") (name "/SAC15") (class "Default")
      (node (ref "C521") (pin "2") (pinfunction "2_2") (pintype "passive"))
      (node (ref "Q516") (pin "3") (pinfunction "C_3") (pintype "passive"))
      (node (ref "R562") (pin "1") (pinfunction "1_1") (pintype "passive"))
      (node (ref "U514") (pin "6") (pinfunction "P2_6") (pintype "passive"))
    )
    (net (code "26") (name "/SAC16") (class "Default")
      (node (ref "C523") (pin "2") (pinfunction "2_2") (pintype "passive"))
      (node (ref "Q503") (pin "3") (pinfunction "C_3") (pintype "passive"))
      (node (ref "R507") (pin "1") (pinfunction "1_1") (pintype "passive"))
      (node (ref "U514") (pin "9") (pinfunction "P4_9") (pintype "passive"))
    )
    (net (code "27") (name "/SAC17") (class "Default")
      (node (ref "C525") (pin "2") (pinfunction "2_2") (pintype "passive"))
      (node (ref "Q507") (pin "3") (pinfunction "C_3") (pintype "passive"))
      (node (ref "R523") (pin "1") (pinfunction "1_1") (pintype "passive"))
      (node (ref "U514") (pin "11") (pinfunction "P6_11") (pintype "passive"))
    )
    (net (code "28") (name "/SAC20") (class "Default")
      (node (ref "C510") (pin "2") (pinfunction "2_2") (pintype "passive"))
      (node (ref "Q502") (pin "3") (pinfunction "C_3") (pintype "passive"))
      (node (ref "R506") (pin "1") (pinfunction "1_1") (pintype "passive"))
      (node (ref "U511") (pin "5") (pinfunction "P1_5") (pintype "passive"))
    )
    (net (code "29") (name "/SAC21") (class "Default")
      (node (ref "C512") (pin "2") (pinfunction "2_2") (pintype "passive"))
      (node (ref "Q506") (pin "3") (pinfunction "C_3") (pintype "passive"))
      (node (ref "R522") (pin "1") (pinfunction "1_1") (pintype "passive"))
      (node (ref "U511") (pin "7") (pinfunction "P3_7") (pintype "passive"))
    )
    (net (code "30") (name "/SAC22") (class "Default")
      (node (ref "C514") (pin "2") (pinfunction "2_2") (pintype "passive"))
      (node (ref "Q510") (pin "3") (pinfunction "C_3") (pintype "passive"))
      (node (ref "R536") (pin "1") (pinfunction "1_1") (pintype "passive"))
      (node (ref "U511") (pin "10") (pinfunction "P5_10") (pintype "passive"))
    )
    (net (code "31") (name "/SAC23") (class "Default")
      (node (ref "C516") (pin "2") (pinfunction "2_2") (pintype "passive"))
      (node (ref "Q512") (pin "3") (pinfunction "C_3") (pintype "passive"))
      (node (ref "R544") (pin "1") (pinfunction "1_1") (pintype "passive"))
      (node (ref "U511") (pin "12") (pinfunction "P7_12") (pintype "passive"))
    )
    (net (code "32") (name "/SAC24") (class "Default")
      (node (ref "C520") (pin "2") (pinfunction "2_2") (pintype "passive"))
      (node (ref "Q514") (pin "3") (pinfunction "C_3") (pintype "passive"))
      (node (ref "R552") (pin "1") (pinfunction "1_1") (pintype "passive"))
      (node (ref "U514") (pin "5") (pinfunction "P1_5") (pintype "passive"))
    )
    (net (code "33") (name "/SAC25") (class "Default")
      (node (ref "C522") (pin "2") (pinfunction "2_2") (pintype "passive"))
      (node (ref "Q517") (pin "3") (pinfunction "C_3") (pintype "passive"))
      (node (ref "R563") (pin "1") (pinfunction "1_1") (pintype "passive"))
      (node (ref "U514") (pin "7") (pinfunction "P3_7") (pintype "passive"))
    )
    (net (code "34") (name "/SAC26") (class "Default")
      (node (ref "C524") (pin "2") (pinfunction "2_2") (pintype "passive"))
      (node (ref "Q504") (pin "3") (pinfunction "C_3") (pintype "passive"))
      (node (ref "R508") (pin "1") (pinfunction "1_1") (pintype "passive"))
      (node (ref "U514") (pin "10") (pinfunction "P5_10") (pintype "passive"))
    )
    (net (code "35") (name "/SAC27") (class "Default")
      (node (ref "C526") (pin "2") (pinfunction "2_2") (pintype "passive"))
      (node (ref "Q508") (pin "3") (pinfunction "C_3") (pintype "passive"))
      (node (ref "R524") (pin "1") (pinfunction "1_1") (pintype "passive"))
      (node (ref "U514") (pin "12") (pinfunction "P7_12") (pintype "passive"))
    )
    (net (code "36") (name "3V3_EXT") (class "Default")
      (node (ref "C527") (pin "1") (pinfunction "1_1") (pintype "passive"))
      (node (ref "C528") (pin "1") (pinfunction "1_1") (pintype "passive"))
      (node (ref "C533") (pin "1") (pinfunction "1_1") (pintype "passive"))
      (node (ref "C534") (pin "1") (pinfunction "1_1") (pintype "passive"))
      (node (ref "C556") (pin "1") (pinfunction "1_1") (pintype "passive"))
      (node (ref "C557") (pin "1") (pinfunction "1_1") (pintype "passive"))
      (node (ref "C558") (pin "1") (pinfunction "1_1") (pintype "passive"))
      (node (ref "C559") (pin "1") (pinfunction "1_1") (pintype "passive"))
      (node (ref "C560") (pin "1") (pinfunction "1_1") (pintype "passive"))
      (node (ref "R505") (pin "2") (pinfunction "2_2") (pintype "passive"))
      (node (ref "R506") (pin "2") (pinfunction "2_2") (pintype "passive"))
      (node (ref "R507") (pin "2") (pinfunction "2_2") (pintype "passive"))
      (node (ref "R508") (pin "2") (pinfunction "2_2") (pintype "passive"))
      (node (ref "R521") (pin "2") (pinfunction "2_2") (pintype "passive"))
      (node (ref "R522") (pin "2") (pinfunction "2_2") (pintype "passive"))
      (node (ref "R523") (pin "2") (pinfunction "2_2") (pintype "passive"))
      (node (ref "R524") (pin "2") (pinfunction "2_2") (pintype "passive"))
      (node (ref "R535") (pin "2") (pinfunction "2_2") (pintype "passive"))
      (node (ref "R536") (pin "2") (pinfunction "2_2") (pintype "passive"))
      (node (ref "R543") (pin "2") (pinfunction "2_2") (pintype "passive"))
      (node (ref "R544") (pin "2") (pinfunction "2_2") (pintype "passive"))
      (node (ref "R551") (pin "2") (pinfunction "2_2") (pintype "passive"))
      (node (ref "R552") (pin "2") (pinfunction "2_2") (pintype "passive"))
      (node (ref "R558") (pin "2") (pinfunction "2_2") (pintype "passive"))
      (node (ref "R562") (pin "2") (pinfunction "2_2") (pintype "passive"))
      (node (ref "R563") (pin "2") (pinfunction "2_2") (pintype "passive"))
      (node (ref "U501") (pin "4") (pinfunction "C_4") (pintype "passive"))
      (node (ref "U502") (pin "4") (pinfunction "C_4") (pintype "passive"))
      (node (ref "U503") (pin "4") (pinfunction "C_4") (pintype "passive"))
      (node (ref "U504") (pin "4") (pinfunction "C_4") (pintype "passive"))
      (node (ref "U505") (pin "4") (pinfunction "C_4") (pintype "passive"))
      (node (ref "U506") (pin "4") (pinfunction "C_4") (pintype "passive"))
      (node (ref "U507") (pin "4") (pinfunction "C_4") (pintype "passive"))
      (node (ref "U508") (pin "4") (pinfunction "C_4") (pintype "passive"))
      (node (ref "U509") (pin "4") (pinfunction "C_4") (pintype "passive"))
      (node (ref "U510") (pin "4") (pinfunction "C_4") (pintype "passive"))
      (node (ref "U511") (pin "16") (pinfunction "VDD_16") (pintype "passive"))
      (node (ref "U512") (pin "4") (pinfunction "C_4") (pintype "passive"))
      (node (ref "U513") (pin "4") (pinfunction "C_4") (pintype "passive"))
      (node (ref "U514") (pin "16") (pinfunction "VDD_16") (pintype "passive"))
      (node (ref "U514") (pin "3") (pinfunction "A2_3") (pintype "passive"))
      (node (ref "U515") (pin "4") (pinfunction "C_4") (pintype "passive"))
      (node (ref "U516") (pin "4") (pinfunction "C_4") (pintype "passive"))
      (node (ref "U517") (pin "4") (pinfunction "C_4") (pintype "passive"))
      (node (ref "U518") (pin "4") (pinfunction "C_4") (pintype "passive"))
      (node (ref "U519") (pin "4") (pinfunction "C_4") (pintype "passive"))
    )
    (net (code "37") (name "ACL") (class "Default")
      (node (ref "R557") (pin "1") (pinfunction "1_1") (pintype "passive"))
    )
    (net (code "38") (name "ACN") (class "Default")
      (node (ref "R509") (pin "1") (pinfunction "1_1") (pintype "passive"))
      (node (ref "R510") (pin "1") (pinfunction "1_1") (pintype "passive"))
      (node (ref "R511") (pin "1") (pinfunction "1_1") (pintype "passive"))
      (node (ref "R512") (pin "1") (pinfunction "1_1") (pintype "passive"))
      (node (ref "R525") (pin "1") (pinfunction "1_1") (pintype "passive"))
      (node (ref "R526") (pin "1") (pinfunction "1_1") (pintype "passive"))
      (node (ref "R527") (pin "1") (pinfunction "1_1") (pintype "passive"))
      (node (ref "R528") (pin "1") (pinfunction "1_1") (pintype "passive"))
      (node (ref "R537") (pin "1") (pinfunction "1_1") (pintype "passive"))
      (node (ref "R538") (pin "1") (pinfunction "1_1") (pintype "passive"))
      (node (ref "R545") (pin "1") (pinfunction "1_1") (pintype "passive"))
      (node (ref "R546") (pin "1") (pinfunction "1_1") (pintype "passive"))
      (node (ref "R553") (pin "1") (pinfunction "1_1") (pintype "passive"))
      (node (ref "R554") (pin "1") (pinfunction "1_1") (pintype "passive"))
      (node (ref "R559") (pin "1") (pinfunction "1_1") (pintype "passive"))
      (node (ref "R564") (pin "1") (pinfunction "1_1") (pintype "passive"))
      (node (ref "R565") (pin "1") (pinfunction "1_1") (pintype "passive"))
    )
    (net (code "39") (name "GND") (class "Default")
      (node (ref "C501") (pin "2") (pinfunction "2_2") (pintype "passive"))
      (node (ref "C502") (pin "2") (pinfunction "2_2") (pintype "passive"))
      (node (ref "C503") (pin "2") (pinfunction "2_2") (pintype "passive"))
      (node (ref "C504") (pin "2") (pinfunction "2_2") (pintype "passive"))
      (node (ref "C505") (pin "2") (pinfunction "2_2") (pintype "passive"))
      (node (ref "C506") (pin "2") (pinfunction "2_2") (pintype "passive"))
      (node (ref "C507") (pin "2") (pinfunction "2_2") (pintype "passive"))
      (node (ref "C508") (pin "2") (pinfunction "2_2") (pintype "passive"))
      (node (ref "C509") (pin "1") (pinfunction "1_1") (pintype "passive"))
      (node (ref "C510") (pin "1") (pinfunction "1_1") (pintype "passive"))
      (node (ref "C511") (pin "1") (pinfunction "1_1") (pintype "passive"))
      (node (ref "C512") (pin "1") (pinfunction "1_1") (pintype "passive"))
      (node (ref "C513") (pin "1") (pinfunction "1_1") (pintype "passive"))
      (node (ref "C514") (pin "1") (pinfunction "1_1") (pintype "passive"))
      (node (ref "C515") (pin "1") (pinfunction "1_1") (pintype "passive"))
      (node (ref "C516") (pin "1") (pinfunction "1_1") (pintype "passive"))
      (node (ref "C517") (pin "2") (pinfunction "2_2") (pintype "passive"))
      (node (ref "C518") (pin "2") (pinfunction "2_2") (pintype "passive"))
      (node (ref "C519") (pin "1") (pinfunction "1_1") (pintype "passive"))
      (node (ref "C520") (pin "1") (pinfunction "1_1") (pintype "passive"))
      (node (ref "C521") (pin "1") (pinfunction "1_1") (pintype "passive"))
      (node (ref "C522") (pin "1") (pinfunction "1_1") (pintype "passive"))
      (node (ref "C523") (pin "1") (pinfunction "1_1") (pintype "passive"))
      (node (ref "C524") (pin "1") (pinfunction "1_1") (pintype "passive"))
      (node (ref "C525") (pin "1") (pinfunction "1_1") (pintype "passive"))
      (node (ref "C526") (pin "1") (pinfunction "1_1") (pintype "passive"))
      (node (ref "C527") (pin "2") (pinfunction "2_2") (pintype "passive"))
      (node (ref "C528") (pin "2") (pinfunction "2_2") (pintype "passive"))
      (node (ref "C529") (pin "2") (pinfunction "2_2") (pintype "passive"))
      (node (ref "C530") (pin "2") (pinfunction "2_2") (pintype "passive"))
      (node (ref "C531") (pin "2") (pinfunction "2_2") (pintype "passive"))
      (node (ref "C532") (pin "2") (pinfunction "2_2") (pintype "passive"))
      (node (ref "C533") (pin "2") (pinfunction "2_2") (pintype "passive"))
      (node (ref "C534") (pin "2") (pinfunction "2_2") (pintype "passive"))
      (node (ref "C535") (pin "2") (pinfunction "2_2") (pintype "passive"))
      (node (ref "C536") (pin "2") (pinfunction "2_2") (pintype "passive"))
      (node (ref "C537") (pin "2") (pinfunction "2_2") (pintype "passive"))
      (node (ref "C538") (pin "1") (pinfunction "1_1") (pintype "passive"))
      (node (ref "C539") (pin "2") (pinfunction "2_2") (pintype "passive"))
      (node (ref "C540") (pin "2") (pinfunction "2_2") (pintype "passive"))
      (node (ref "C541") (pin "2") (pinfunction "2_2") (pintype "passive"))
      (node (ref "C542") (pin "2") (pinfunction "2_2") (pintype "passive"))
      (node (ref "C543") (pin "2") (pinfunction "2_2") (pintype "passive"))
      (node (ref "C544") (pin "2") (pinfunction "2_2") (pintype "passive"))
      (node (ref "C545") (pin "2") (pinfunction "2_2") (pintype "passive"))
      (node (ref "C546") (pin "2") (pinfunction "2_2") (pintype "passive"))
      (node (ref "C547") (pin "2") (pinfunction "2_2") (pintype "passive"))
      (node (ref "C548") (pin "2") (pinfunction "2_2") (pintype "passive"))
      (node (ref "C549") (pin "2") (pinfunction "2_2") (pintype "passive"))
      (node (ref "C550") (pin "2") (pinfunction "2_2") (pintype "passive"))
      (node (ref "C551") (pin "2") (pinfunction "2_2") (pintype "passive"))
      (node (ref "C552") (pin "2") (pinfunction "2_2") (pintype "passive"))
      (node (ref "C553") (pin "2") (pinfunction "2_2") (pintype "passive"))
      (node (ref "C554") (pin "2") (pinfunction "2_2") (pintype "passive"))
      (node (ref "C555") (pin "2") (pinfunction "2_2") (pintype "passive"))
      (node (ref "C556") (pin "2") (pinfunction "2_2") (pintype "passive"))
      (node (ref "C557") (pin "2") (pinfunction "2_2") (pintype "passive"))
      (node (ref "C558") (pin "2") (pinfunction "2_2") (pintype "passive"))
      (node (ref "C559") (pin "2") (pinfunction "2_2") (pintype "passive"))
      (node (ref "C560") (pin "2") (pinfunction "2_2") (pintype "passive"))
      (node (ref "Q501") (pin "2") (pinfunction "E_2") (pintype "passive"))
      (node (ref "Q502") (pin "2") (pinfunction "E_2") (pintype "passive"))
      (node (ref "Q503") (pin "2") (pinfunction "E_2") (pintype "passive"))
      (node (ref "Q504") (pin "2") (pinfunction "E_2") (pintype "passive"))
      (node (ref "Q505") (pin "2") (pinfunction "E_2") (pintype "passive"))
      (node (ref "Q506") (pin "2") (pinfunction "E_2") (pintype "passive"))
      (node (ref "Q507") (pin "2") (pinfunction "E_2") (pintype "passive"))
      (node (ref "Q508") (pin "2") (pinfunction "E_2") (pintype "passive"))
      (node (ref "Q509") (pin "2") (pinfunction "E_2") (pintype "passive"))
      (node (ref "Q510") (pin "2") (pinfunction "E_2") (pintype "passive"))
      (node (ref "Q511") (pin "2") (pinfunction "E_2") (pintype "passive"))
      (node (ref "Q512") (pin "2") (pinfunction "E_2") (pintype "passive"))
      (node (ref "Q513") (pin "2") (pinfunction "E_2") (pintype "passive"))
      (node (ref "Q514") (pin "2") (pinfunction "E_2") (pintype "passive"))
      (node (ref "Q515") (pin "2") (pinfunction "E_2") (pintype "passive"))
      (node (ref "Q516") (pin "2") (pinfunction "E_2") (pintype "passive"))
      (node (ref "Q517") (pin "2") (pinfunction "E_2") (pintype "passive"))
      (node (ref "R513") (pin "1") (pinfunction "1_1") (pintype "passive"))
      (node (ref "R514") (pin "1") (pinfunction "1_1") (pintype "passive"))
      (node (ref "R515") (pin "1") (pinfunction "1_1") (pintype "passive"))
      (node (ref "R516") (pin "1") (pinfunction "1_1") (pintype "passive"))
      (node (ref "R529") (pin "1") (pinfunction "1_1") (pintype "passive"))
      (node (ref "R530") (pin "1") (pinfunction "1_1") (pintype "passive"))
      (node (ref "R531") (pin "1") (pinfunction "1_1") (pintype "passive"))
      (node (ref "R532") (pin "1") (pinfunction "1_1") (pintype "passive"))
      (node (ref "R539") (pin "1") (pinfunction "1_1") (pintype "passive"))
      (node (ref "R540") (pin "1") (pinfunction "1_1") (pintype "passive"))
      (node (ref "R547") (pin "1") (pinfunction "1_1") (pintype "passive"))
      (node (ref "R548") (pin "1") (pinfunction "1_1") (pintype "passive"))
      (node (ref "R555") (pin "1") (pinfunction "1_1") (pintype "passive"))
      (node (ref "R556") (pin "1") (pinfunction "1_1") (pintype "passive"))
      (node (ref "R566") (pin "1") (pinfunction "1_1") (pintype "passive"))
      (node (ref "R567") (pin "1") (pinfunction "1_1") (pintype "passive"))
      (node (ref "R568") (pin "1") (pinfunction "1_1") (pintype "passive"))
      (node (ref "U511") (pin "1") (pinfunction "A0_1") (pintype "passive"))
      (node (ref "U511") (pin "2") (pinfunction "A1_2") (pintype "passive"))
      (node (ref "U511") (pin "3") (pinfunction "A2_3") (pintype "passive"))
      (node (ref "U511") (pin "8") (pinfunction "VSS_8") (pintype "passive"))
      (node (ref "U514") (pin "1") (pinfunction "A0_1") (pintype "passive"))
      (node (ref "U514") (pin "2") (pinfunction "A1_2") (pintype "passive"))
      (node (ref "U514") (pin "8") (pinfunction "VSS_8") (pintype "passive"))
    )
    (net (code "40") (name "Net-(Q501-B)") (class "Default")
      (node (ref "Q501") (pin "1") (pinfunction "B_1") (pintype "passive"))
      (node (ref "R569") (pin "1") (pinfunction "1_1") (pintype "passive"))
    )
    (net (code "41") (name "Net-(Q502-B)") (class "Default")
      (node (ref "Q502") (pin "1") (pinfunction "B_1") (pintype "passive"))
      (node (ref "R570") (pin "1") (pinfunction "1_1") (pintype "passive"))
    )
    (net (code "42") (name "Net-(Q503-B)") (class "Default")
      (node (ref "Q503") (pin "1") (pinfunction "B_1") (pintype "passive"))
      (node (ref "R571") (pin "1") (pinfunction "1_1") (pintype "passive"))
    )
    (net (code "43") (name "Net-(Q504-B)") (class "Default")
      (node (ref "Q504") (pin "1") (pinfunction "B_1") (pintype "passive"))
      (node (ref "R572") (pin "1") (pinfunction "1_1") (pintype "passive"))
    )
    (net (code "44") (name "Net-(Q505-B)") (class "Default")
      (node (ref "Q505") (pin "1") (pinfunction "B_1") (pintype "passive"))
      (node (ref "R573") (pin "1") (pinfunction "1_1") (pintype "passive"))
    )
    (net (code "45") (name "Net-(Q506-B)") (class "Default")
      (node (ref "Q506") (pin "1") (pinfunction "B_1") (pintype "passive"))
      (node (ref "R574") (pin "1") (pinfunction "1_1") (pintype "passive"))
    )
    (net (code "46") (name "Net-(Q507-B)") (class "Default")
      (node (ref "Q507") (pin "1") (pinfunction "B_1") (pintype "passive"))
      (node (ref "R575") (pin "1") (pinfunction "1_1") (pintype "passive"))
    )
    (net (code "47") (name "Net-(Q508-B)") (class "Default")
      (node (ref "Q508") (pin "1") (pinfunction "B_1") (pintype "passive"))
      (node (ref "R576") (pin "1") (pinfunction "1_1") (pintype "passive"))
    )
    (net (code "48") (name "Net-(Q509-B)") (class "Default")
      (node (ref "Q509") (pin "1") (pinfunction "B_1") (pintype "passive"))
      (node (ref "R577") (pin "1") (pinfunction "1_1") (pintype "passive"))
    )
    (net (code "49") (name "Net-(Q510-B)") (class "Default")
      (node (ref "Q510") (pin "1") (pinfunction "B_1") (pintype "passive"))
      (node (ref "R578") (pin "1") (pinfunction "1_1") (pintype "passive"))
    )
    (net (code "50") (name "Net-(Q511-B)") (class "Default")
      (node (ref "Q511") (pin "1") (pinfunction "B_1") (pintype "passive"))
      (node (ref "R579") (pin "1") (pinfunction "1_1") (pintype "passive"))
    )
    (net (code "51") (name "Net-(Q512-B)") (class "Default")
      (node (ref "Q512") (pin "1") (pinfunction "B_1") (pintype "passive"))
      (node (ref "R580") (pin "1") (pinfunction "1_1") (pintype "passive"))
    )
    (net (code "52") (name "Net-(Q513-B)") (class "Default")
      (node (ref "Q513") (pin "1") (pinfunction "B_1") (pintype "passive"))
      (node (ref "R581") (pin "1") (pinfunction "1_1") (pintype "passive"))
    )
    (net (code "53") (name "Net-(Q514-B)") (class "Default")
      (node (ref "Q514") (pin "1") (pinfunction "B_1") (pintype "passive"))
      (node (ref "R582") (pin "1") (pinfunction "1_1") (pintype "passive"))
    )
    (net (code "54") (name "Net-(Q515-B)") (class "Default")
      (node (ref "Q515") (pin "1") (pinfunction "B_1") (pintype "passive"))
      (node (ref "R583") (pin "1") (pinfunction "1_1") (pintype "passive"))
    )
    (net (code "55") (name "Net-(Q516-B)") (class "Default")
      (node (ref "Q516") (pin "1") (pinfunction "B_1") (pintype "passive"))
      (node (ref "R584") (pin "1") (pinfunction "1_1") (pintype "passive"))
    )
    (net (code "56") (name "Net-(Q517-B)") (class "Default")
      (node (ref "Q517") (pin "1") (pinfunction "B_1") (pintype "passive"))
      (node (ref "R585") (pin "1") (pinfunction "1_1") (pintype "passive"))
    )
    (net (code "57") (name "Net-(U501-A{slash}C)") (class "Default")
      (node (ref "R501") (pin "2") (pinfunction "2_2") (pintype "passive"))
      (node (ref "U501") (pin "1") (pinfunction "A/C_1") (pintype "passive"))
    )
    (net (code "58") (name "Net-(U501-C{slash}A)") (class "Default")
      (node (ref "R509") (pin "2") (pinfunction "2_2") (pintype "passive"))
      (node (ref "U501") (pin "2") (pinfunction "C/A_2") (pintype "passive"))
    )
    (net (code "59") (name "Net-(U501-E)") (class "Default")
      (node (ref "C501") (pin "1") (pinfunction "1_1") (pintype "passive"))
      (node (ref "C539") (pin "1") (pinfunction "1_1") (pintype "passive"))
      (node (ref "R513") (pin "2") (pinfunction "2_2") (pintype "passive"))
      (node (ref "R569") (pin "2") (pinfunction "2_2") (pintype "passive"))
      (node (ref "U501") (pin "3") (pinfunction "E_3") (pintype "passive"))
    )
    (net (code "60") (name "Net-(U502-A{slash}C)") (class "Default")
      (node (ref "R502") (pin "2") (pinfunction "2_2") (pintype "passive"))
      (node (ref "U502") (pin "1") (pinfunction "A/C_1") (pintype "passive"))
    )
    (net (code "61") (name "Net-(U502-C{slash}A)") (class "Default")
      (node (ref "R510") (pin "2") (pinfunction "2_2") (pintype "passive"))
      (node (ref "U502") (pin "2") (pinfunction "C/A_2") (pintype "passive"))
    )
    (net (code "62") (name "Net-(U502-E)") (class "Default")
      (node (ref "C502") (pin "1") (pinfunction "1_1") (pintype "passive"))
      (node (ref "C540") (pin "1") (pinfunction "1_1") (pintype "passive"))
      (node (ref "R514") (pin "2") (pinfunction "2_2") (pintype "passive"))
      (node (ref "R570") (pin "2") (pinfunction "2_2") (pintype "passive"))
      (node (ref "U502") (pin "3") (pinfunction "E_3") (pintype "passive"))
    )
    (net (code "63") (name "Net-(U503-A{slash}C)") (class "Default")
      (node (ref "R503") (pin "2") (pinfunction "2_2") (pintype "passive"))
      (node (ref "U503") (pin "1") (pinfunction "A/C_1") (pintype "passive"))
    )
    (net (code "64") (name "Net-(U503-C{slash}A)") (class "Default")
      (node (ref "R511") (pin "2") (pinfunction "2_2") (pintype "passive"))
      (node (ref "U503") (pin "2") (pinfunction "C/A_2") (pintype "passive"))
    )
    (net (code "65") (name "Net-(U503-E)") (class "Default")
      (node (ref "C503") (pin "1") (pinfunction "1_1") (pintype "passive"))
      (node (ref "C541") (pin "1") (pinfunction "1_1") (pintype "passive"))
      (node (ref "R515") (pin "2") (pinfunction "2_2") (pintype "passive"))
      (node (ref "R571") (pin "2") (pinfunction "2_2") (pintype "passive"))
      (node (ref "U503") (pin "3") (pinfunction "E_3") (pintype "passive"))
    )
    (net (code "66") (name "Net-(U504-A{slash}C)") (class "Default")
      (node (ref "R504") (pin "2") (pinfunction "2_2") (pintype "passive"))
      (node (ref "U504") (pin "1") (pinfunction "A/C_1") (pintype "passive"))
    )
    (net (code "67") (name "Net-(U504-C{slash}A)") (class "Default")
      (node (ref "R512") (pin "2") (pinfunction "2_2") (pintype "passive"))
      (node (ref "U504") (pin "2") (pinfunction "C/A_2") (pintype "passive"))
    )
    (net (code "68") (name "Net-(U504-E)") (class "Default")
      (node (ref "C504") (pin "1") (pinfunction "1_1") (pintype "passive"))
      (node (ref "C542") (pin "1") (pinfunction "1_1") (pintype "passive"))
      (node (ref "R516") (pin "2") (pinfunction "2_2") (pintype "passive"))
      (node (ref "R572") (pin "2") (pinfunction "2_2") (pintype "passive"))
      (node (ref "U504") (pin "3") (pinfunction "E_3") (pintype "passive"))
    )
    (net (code "69") (name "Net-(U505-A{slash}C)") (class "Default")
      (node (ref "R517") (pin "2") (pinfunction "2_2") (pintype "passive"))
      (node (ref "U505") (pin "1") (pinfunction "A/C_1") (pintype "passive"))
    )
    (net (code "70") (name "Net-(U505-C{slash}A)") (class "Default")
      (node (ref "R525") (pin "2") (pinfunction "2_2") (pintype "passive"))
      (node (ref "U505") (pin "2") (pinfunction "C/A_2") (pintype "passive"))
    )
    (net (code "71") (name "Net-(U505-E)") (class "Default")
      (node (ref "C505") (pin "1") (pinfunction "1_1") (pintype "passive"))
      (node (ref "C543") (pin "1") (pinfunction "1_1") (pintype "passive"))
      (node (ref "R529") (pin "2") (pinfunction "2_2") (pintype "passive"))
      (node (ref "R573") (pin "2") (pinfunction "2_2") (pintype "passive"))
      (node (ref "U505") (pin "3") (pinfunction "E_3") (pintype "passive"))
    )
    (net (code "72") (name "Net-(U506-A{slash}C)") (class "Default")
      (node (ref "R518") (pin "2") (pinfunction "2_2") (pintype "passive"))
      (node (ref "U506") (pin "1") (pinfunction "A/C_1") (pintype "passive"))
    )
    (net (code "73") (name "Net-(U506-C{slash}A)") (class "Default")
      (node (ref "R526") (pin "2") (pinfunction "2_2") (pintype "passive"))
      (node (ref "U506") (pin "2") (pinfunction "C/A_2") (pintype "passive"))
    )
    (net (code "74") (name "Net-(U506-E)") (class "Default")
      (node (ref "C506") (pin "1") (pinfunction "1_1") (pintype "passive"))
      (node (ref "C544") (pin "1") (pinfunction "1_1") (pintype "passive"))
      (node (ref "R530") (pin "2") (pinfunction "2_2") (pintype "passive"))
      (node (ref "R574") (pin "2") (pinfunction "2_2") (pintype "passive"))
      (node (ref "U506") (pin "3") (pinfunction "E_3") (pintype "passive"))
    )
    (net (code "75") (name "Net-(U507-A{slash}C)") (class "Default")
      (node (ref "R519") (pin "2") (pinfunction "2_2") (pintype "passive"))
      (node (ref "U507") (pin "1") (pinfunction "A/C_1") (pintype "passive"))
    )
    (net (code "76") (name "Net-(U507-C{slash}A)") (class "Default")
      (node (ref "R527") (pin "2") (pinfunction "2_2") (pintype "passive"))
      (node (ref "U507") (pin "2") (pinfunction "C/A_2") (pintype "passive"))
    )
    (net (code "77") (name "Net-(U507-E)") (class "Default")
      (node (ref "C507") (pin "1") (pinfunction "1_1") (pintype "passive"))
      (node (ref "C545") (pin "1") (pinfunction "1_1") (pintype "passive"))
      (node (ref "R531") (pin "2") (pinfunction "2_2") (pintype "passive"))
      (node (ref "R575") (pin "2") (pinfunction "2_2") (pintype "passive"))
      (node (ref "U507") (pin "3") (pinfunction "E_3") (pintype "passive"))
    )
    (net (code "78") (name "Net-(U508-A{slash}C)") (class "Default")
      (node (ref "R520") (pin "2") (pinfunction "2_2") (pintype "passive"))
      (node (ref "U508") (pin "1") (pinfunction "A/C_1") (pintype "passive"))
    )
    (net (code "79") (name "Net-(U508-C{slash}A)") (class "Default")
      (node (ref "R528") (pin "2") (pinfunction "2_2") (pintype "passive"))
      (node (ref "U508") (pin "2") (pinfunction "C/A_2") (pintype "passive"))
    )
    (net (code "80") (name "Net-(U508-E)") (class "Default")
      (node (ref "C508") (pin "1") (pinfunction "1_1") (pintype "passive"))
      (node (ref "C546") (pin "1") (pinfunction "1_1") (pintype "passive"))
      (node (ref "R532") (pin "2") (pinfunction "2_2") (pintype "passive"))
      (node (ref "R576") (pin "2") (pinfunction "2_2") (pintype "passive"))
      (node (ref "U508") (pin "3") (pinfunction "E_3") (pintype "passive"))
    )
    (net (code "81") (name "Net-(U509-A{slash}C)") (class "Default")
      (node (ref "R533") (pin "2") (pinfunction "2_2") (pintype "passive"))
      (node (ref "U509") (pin "1") (pinfunction "A/C_1") (pintype "passive"))
    )
    (net (code "82") (name "Net-(U509-C{slash}A)") (class "Default")
      (node (ref "R537") (pin "2") (pinfunction "2_2") (pintype "passive"))
      (node (ref "U509") (pin "2") (pinfunction "C/A_2") (pintype "passive"))
    )
    (net (code "83") (name "Net-(U509-E)") (class "Default")
      (node (ref "C517") (pin "1") (pinfunction "1_1") (pintype "passive"))
      (node (ref "C547") (pin "1") (pinfunction "1_1") (pintype "passive"))
      (node (ref "R539") (pin "2") (pinfunction "2_2") (pintype "passive"))
      (node (ref "R577") (pin "2") (pinfunction "2_2") (pintype "passive"))
      (node (ref "U509") (pin "3") (pinfunction "E_3") (pintype "passive"))
    )
    (net (code "84") (name "Net-(U510-A{slash}C)") (class "Default")
      (node (ref "R534") (pin "2") (pinfunction "2_2") (pintype "passive"))
      (node (ref "U510") (pin "1") (pinfunction "A/C_1") (pintype "passive"))
    )
    (net (code "85") (name "Net-(U510-C{slash}A)") (class "Default")
      (node (ref "R538") (pin "2") (pinfunction "2_2") (pintype "passive"))
      (node (ref "U510") (pin "2") (pinfunction "C/A_2") (pintype "passive"))
    )
    (net (code "86") (name "Net-(U510-E)") (class "Default")
      (node (ref "C518") (pin "1") (pinfunction "1_1") (pintype "passive"))
      (node (ref "C548") (pin "1") (pinfunction "1_1") (pintype "passive"))
      (node (ref "R540") (pin "2") (pinfunction "2_2") (pintype "passive"))
      (node (ref "R578") (pin "2") (pinfunction "2_2") (pintype "passive"))
      (node (ref "U510") (pin "3") (pinfunction "E_3") (pintype "passive"))
    )
    (net (code "87") (name "Net-(U512-A{slash}C)") (class "Default")
      (node (ref "R541") (pin "2") (pinfunction "2_2") (pintype "passive"))
      (node (ref "U512") (pin "1") (pinfunction "A/C_1") (pintype "passive"))
    )
    (net (code "88") (name "Net-(U512-C{slash}A)") (class "Default")
      (node (ref "R545") (pin "2") (pinfunction "2_2") (pintype "passive"))
      (node (ref "U512") (pin "2") (pinfunction "C/A_2") (pintype "passive"))
    )
    (net (code "89") (name "Net-(U512-E)") (class "Default")
      (node (ref "C529") (pin "1") (pinfunction "1_1") (pintype "passive"))
      (node (ref "C549") (pin "1") (pinfunction "1_1") (pintype "passive"))
      (node (ref "R547") (pin "2") (pinfunction "2_2") (pintype "passive"))
      (node (ref "R579") (pin "2") (pinfunction "2_2") (pintype "passive"))
      (node (ref "U512") (pin "3") (pinfunction "E_3") (pintype "passive"))
    )
    (net (code "90") (name "Net-(U513-A{slash}C)") (class "Default")
      (node (ref "R542") (pin "2") (pinfunction "2_2") (pintype "passive"))
      (node (ref "U513") (pin "1") (pinfunction "A/C_1") (pintype "passive"))
    )
    (net (code "91") (name "Net-(U513-C{slash}A)") (class "Default")
      (node (ref "R546") (pin "2") (pinfunction "2_2") (pintype "passive"))
      (node (ref "U513") (pin "2") (pinfunction "C/A_2") (pintype "passive"))
    )
    (net (code "92") (name "Net-(U513-E)") (class "Default")
      (node (ref "C530") (pin "1") (pinfunction "1_1") (pintype "passive"))
      (node (ref "C550") (pin "1") (pinfunction "1_1") (pintype "passive"))
      (node (ref "R548") (pin "2") (pinfunction "2_2") (pintype "passive"))
      (node (ref "R580") (pin "2") (pinfunction "2_2") (pintype "passive"))
      (node (ref "U513") (pin "3") (pinfunction "E_3") (pintype "passive"))
    )
    (net (code "93") (name "Net-(U515-A{slash}C)") (class "Default")
      (node (ref "R549") (pin "2") (pinfunction "2_2") (pintype "passive"))
      (node (ref "U515") (pin "1") (pinfunction "A/C_1") (pintype "passive"))
    )
    (net (code "94") (name "Net-(U515-C{slash}A)") (class "Default")
      (node (ref "R553") (pin "2") (pinfunction "2_2") (pintype "passive"))
      (node (ref "U515") (pin "2") (pinfunction "C/A_2") (pintype "passive"))
    )
    (net (code "95") (name "Net-(U515-E)") (class "Default")
      (node (ref "C531") (pin "1") (pinfunction "1_1") (pintype "passive"))
      (node (ref "C551") (pin "1") (pinfunction "1_1") (pintype "passive"))
      (node (ref "R555") (pin "2") (pinfunction "2_2") (pintype "passive"))
      (node (ref "R581") (pin "2") (pinfunction "2_2") (pintype "passive"))
      (node (ref "U515") (pin "3") (pinfunction "E_3") (pintype "passive"))
    )
    (net (code "96") (name "Net-(U516-A{slash}C)") (class "Default")
      (node (ref "R550") (pin "2") (pinfunction "2_2") (pintype "passive"))
      (node (ref "U516") (pin "1") (pinfunction "A/C_1") (pintype "passive"))
    )
    (net (code "97") (name "Net-(U516-C{slash}A)") (class "Default")
      (node (ref "R554") (pin "2") (pinfunction "2_2") (pintype "passive"))
      (node (ref "U516") (pin "2") (pinfunction "C/A_2") (pintype "passive"))
    )
    (net (code "98") (name "Net-(U516-E)") (class "Default")
      (node (ref "C532") (pin "1") (pinfunction "1_1") (pintype "passive"))
      (node (ref "C552") (pin "1") (pinfunction "1_1") (pintype "passive"))
      (node (ref "R556") (pin "2") (pinfunction "2_2") (pintype "passive"))
      (node (ref "R582") (pin "2") (pinfunction "2_2") (pintype "passive"))
      (node (ref "U516") (pin "3") (pinfunction "E_3") (pintype "passive"))
    )
    (net (code "99") (name "Net-(U517-A{slash}C)") (class "Default")
      (node (ref "R557") (pin "2") (pinfunction "2_2") (pintype "passive"))
      (node (ref "U517") (pin "1") (pinfunction "A/C_1") (pintype "passive"))
    )
    (net (code "100") (name "Net-(U517-C{slash}A)") (class "Default")
      (node (ref "R559") (pin "2") (pinfunction "2_2") (pintype "passive"))
      (node (ref "U517") (pin "2") (pinfunction "C/A_2") (pintype "passive"))
    )
    (net (code "101") (name "Net-(U517-E)") (class "Default")
      (node (ref "C535") (pin "1") (pinfunction "1_1") (pintype "passive"))
      (node (ref "C555") (pin "1") (pinfunction "1_1") (pintype "passive"))
      (node (ref "R566") (pin "2") (pinfunction "2_2") (pintype "passive"))
      (node (ref "R583") (pin "2") (pinfunction "2_2") (pintype "passive"))
      (node (ref "U517") (pin "3") (pinfunction "E_3") (pintype "passive"))
    )
    (net (code "102") (name "Net-(U518-A{slash}C)") (class "Default")
      (node (ref "R560") (pin "2") (pinfunction "2_2") (pintype "passive"))
      (node (ref "U518") (pin "1") (pinfunction "A/C_1") (pintype "passive"))
    )
    (net (code "103") (name "Net-(U518-C{slash}A)") (class "Default")
      (node (ref "R564") (pin "2") (pinfunction "2_2") (pintype "passive"))
      (node (ref "U518") (pin "2") (pinfunction "C/A_2") (pintype "passive"))
    )
    (net (code "104") (name "Net-(U518-E)") (class "Default")
      (node (ref "C536") (pin "1") (pinfunction "1_1") (pintype "passive"))
      (node (ref "C553") (pin "1") (pinfunction "1_1") (pintype "passive"))
      (node (ref "R567") (pin "2") (pinfunction "2_2") (pintype "passive"))
      (node (ref "R584") (pin "2") (pinfunction "2_2") (pintype "passive"))
      (node (ref "U518") (pin "3") (pinfunction "E_3") (pintype "passive"))
    )
    (net (code "105") (name "Net-(U519-A{slash}C)") (class "Default")
      (node (ref "R561") (pin "2") (pinfunction "2_2") (pintype "passive"))
      (node (ref "U519") (pin "1") (pinfunction "A/C_1") (pintype "passive"))
    )
    (net (code "106") (name "Net-(U519-C{slash}A)") (class "Default")
      (node (ref "R565") (pin "2") (pinfunction "2_2") (pintype "passive"))
      (node (ref "U519") (pin "2") (pinfunction "C/A_2") (pintype "passive"))
    )
    (net (code "107") (name "Net-(U519-E)") (class "Default")
      (node (ref "C537") (pin "1") (pinfunction "1_1") (pintype "passive"))
      (node (ref "C554") (pin "1") (pinfunction "1_1") (pintype "passive"))
      (node (ref "R568") (pin "2") (pinfunction "2_2") (pintype "passive"))
      (node (ref "R585") (pin "2") (pinfunction "2_2") (pintype "passive"))
      (node (ref "U519") (pin "3") (pinfunction "E_3") (pintype "passive"))
    )
    (net (code "108") (name "unconnected-(U511-INT-Pad13)") (class "Default")
      (node (ref "U511") (pin "13") (pinfunction "INT_13") (pintype "passive+no_connect"))
    )
    (net (code "109") (name "unconnected-(U514-INT-Pad13)") (class "Default")
      (node (ref "U514") (pin "13") (pinfunction "INT_13") (pintype "passive+no_connect"))
    )
  )
)
